# WaterLevelDisplay_v1-0.net
KiCad netlist of a schematic drawn in EAGLE
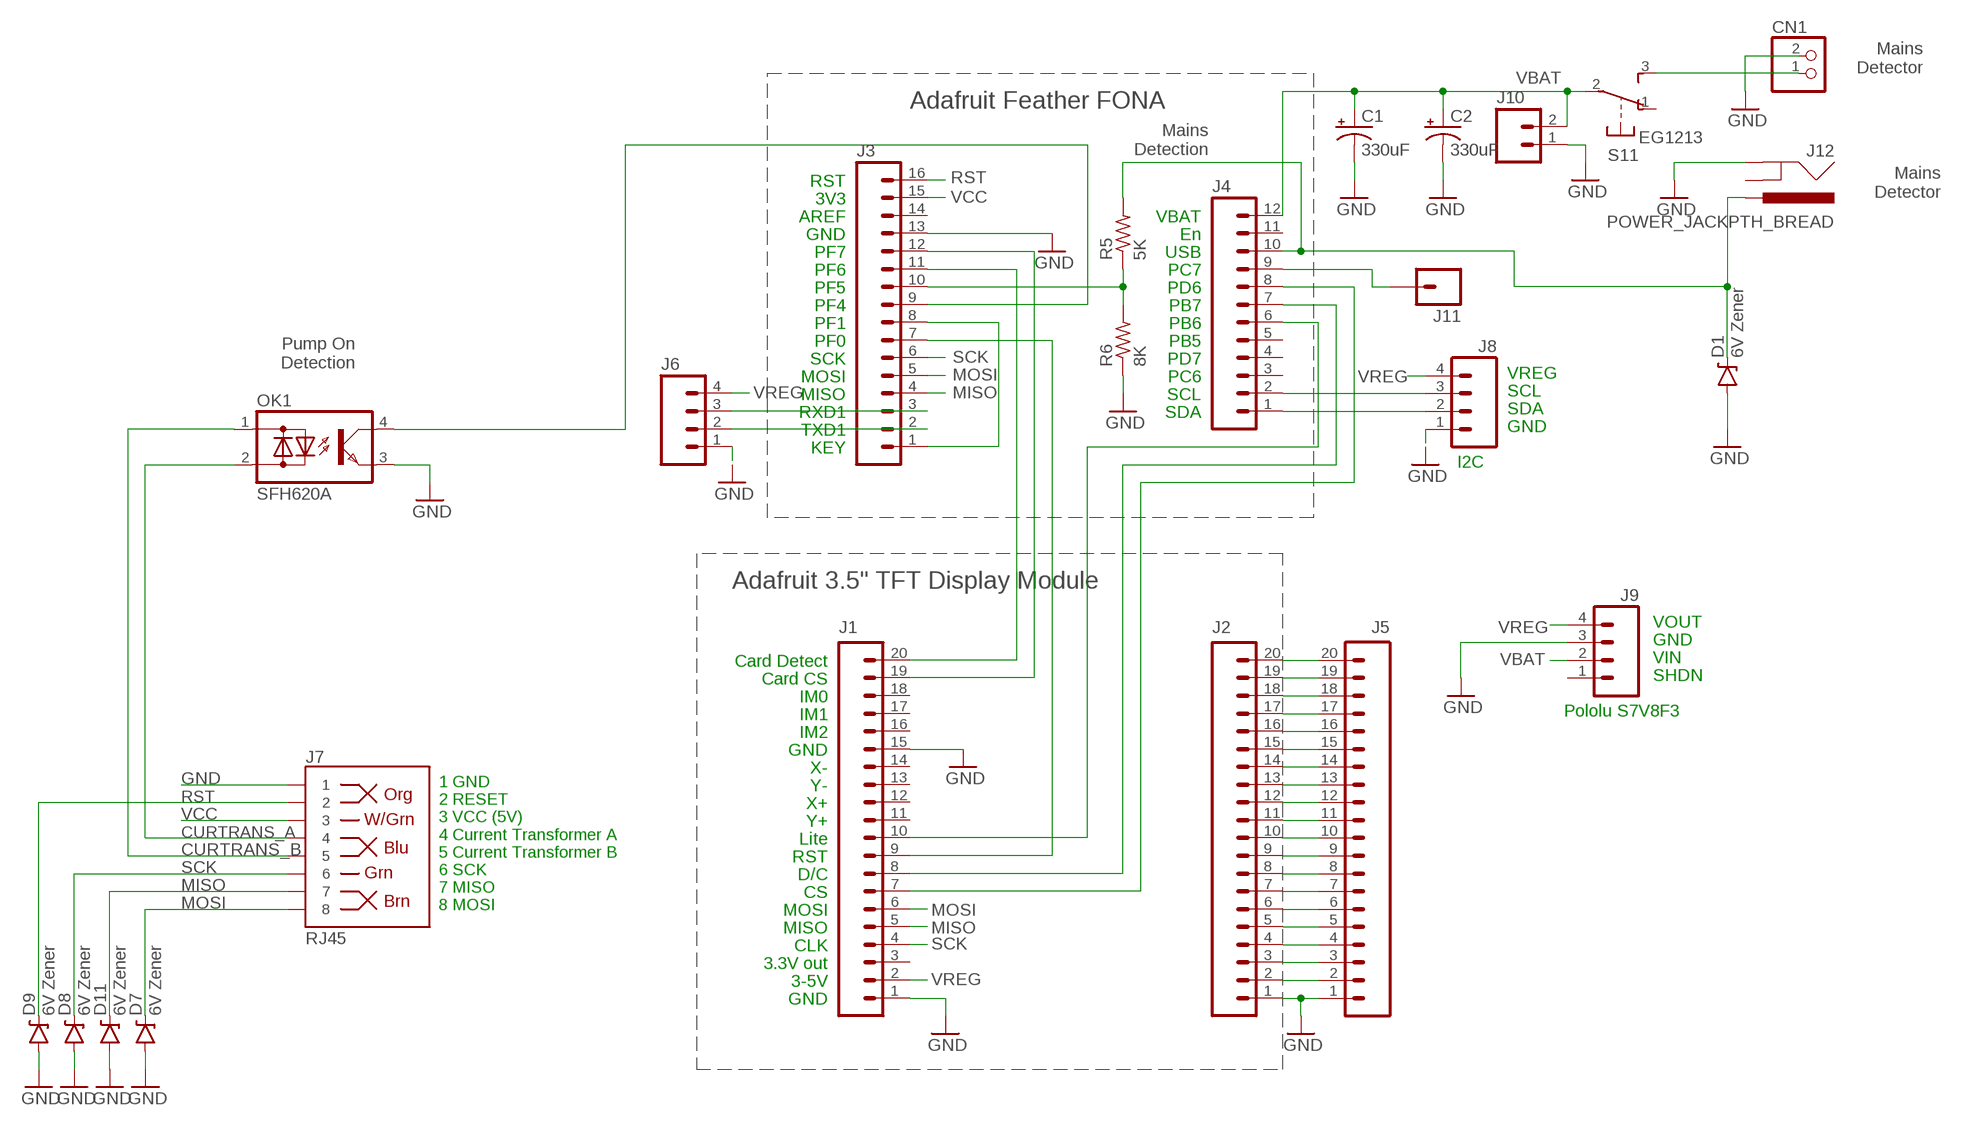
[diagram p0: schematic, sheet 1]

(export (version "E")
  (design (tool "Eeschema 10.0.6"))
  (components
    (comp (ref "C1")
      (value "330uF")
      (footprint "eagle-import:CPOL-RADIAL-100UF-25V")
      (libsource (lib "eagle-import") (part "CAP_POLPTH1"))
    )
    (comp (ref "C2")
      (value "330uF")
      (footprint "eagle-import:CPOL-RADIAL-100UF-25V")
      (libsource (lib "eagle-import") (part "CAP_POLPTH1"))
    )
    (comp (ref "CN1")
      (value "JST_2PIN-SMT-RA")
      (footprint "eagle-import:JST-PH-2-SMT-RA")
      (libsource (lib "eagle-import") (part "JST_2PIN-SMT-RA"))
    )
    (comp (ref "D1")
      (value "6V Zener")
      (footprint "eagle-import:DIODE-ZENER")
      (libsource (lib "eagle-import") (part "DIODE-ZENERPTH"))
    )
    (comp (ref "D7")
      (value "6V Zener")
      (footprint "eagle-import:DIODE-ZENER")
      (libsource (lib "eagle-import") (part "DIODE-ZENERPTH"))
    )
    (comp (ref "D8")
      (value "6V Zener")
      (footprint "eagle-import:DIODE-ZENER")
      (libsource (lib "eagle-import") (part "DIODE-ZENERPTH"))
    )
    (comp (ref "D9")
      (value "6V Zener")
      (footprint "eagle-import:DIODE-ZENER")
      (libsource (lib "eagle-import") (part "DIODE-ZENERPTH"))
    )
    (comp (ref "D11")
      (value "6V Zener")
      (footprint "eagle-import:DIODE-ZENER")
      (libsource (lib "eagle-import") (part "DIODE-ZENERPTH"))
    )
    (comp (ref "J1")
      (value "M20NOSILK")
      (footprint "eagle-import:1X20_NOSILK")
      (libsource (lib "eagle-import") (part "M20NOSILK"))
    )
    (comp (ref "J2")
      (value "M20NOSILK")
      (footprint "eagle-import:1X20_NOSILK")
      (libsource (lib "eagle-import") (part "M20NOSILK"))
    )
    (comp (ref "J3")
      (value "M161X16_NO_SILK")
      (footprint "eagle-import:1X16_NO_SILK")
      (libsource (lib "eagle-import") (part "M161X16_NO_SILK"))
    )
    (comp (ref "J4")
      (value "M12NO_SILK")
      (footprint "eagle-import:1X12_NO_SILK")
      (libsource (lib "eagle-import") (part "M12NO_SILK"))
    )
    (comp (ref "J5")
      (value "M20NOSILK")
      (footprint "eagle-import:1X20_NOSILK")
      (libsource (lib "eagle-import") (part "M20NOSILK"))
    )
    (comp (ref "J6")
      (value "M04PTH")
      (footprint "eagle-import:1X04")
      (libsource (lib "eagle-import") (part "M04PTH"))
    )
    (comp (ref "J7")
      (value "RJ45")
      (footprint "eagle-import:RJ45-8")
      (libsource (lib "eagle-import") (part "RJ45-8PTH"))
    )
    (comp (ref "J8")
      (value "M04PTH")
      (footprint "eagle-import:1X04")
      (libsource (lib "eagle-import") (part "M04PTH"))
    )
    (comp (ref "J9")
      (value "M04PTH")
      (footprint "eagle-import:1X04")
      (libsource (lib "eagle-import") (part "M04PTH"))
    )
    (comp (ref "J10")
      (value "M02PTH")
      (footprint "eagle-import:1X02")
      (libsource (lib "eagle-import") (part "M02PTH"))
    )
    (comp (ref "J11")
      (value "M01PTH")
      (footprint "eagle-import:1X01")
      (libsource (lib "eagle-import") (part "M01PTH"))
    )
    (comp (ref "J12")
      (value "POWER_JACKPTH_BREAD")
      (footprint "eagle-import:POWER_JACK_PTH_BREAD")
      (libsource (lib "eagle-import") (part "POWER_JACKPTH_BREAD"))
    )
    (comp (ref "OK1")
      (value "SFH620A")
      (footprint "eagle-import:DIL04")
      (fields (field (name "MPN") "SFH620A-2"))
      (libsource (lib "eagle-import") (part "SFH620A"))
    )
    (comp (ref "R5")
      (value "5K")
      (footprint "eagle-import:0204_5")
      (libsource (lib "eagle-import") (part "R-US_0204/5"))
    )
    (comp (ref "R6")
      (value "8K")
      (footprint "eagle-import:0204_5")
      (libsource (lib "eagle-import") (part "R-US_0204/5"))
    )
    (comp (ref "S1")
      (value "EG1213")
      (footprint "eagle-import:EG1213")
      (libsource (lib "eagle-import") (part "EG1213"))
    )
  )
  (nets
    (net (code "1") (name "/CURTRANS_A") (class "Default")
      (node (ref "J7") (pin "4") (pinfunction "4_4") (pintype "bidirectional"))
      (node (ref "OK1") (pin "2") (pinfunction "AC2_2") (pintype "passive"))
    )
    (net (code "2") (name "/CURTRANS_B") (class "Default")
      (node (ref "J7") (pin "5") (pinfunction "5_5") (pintype "bidirectional"))
      (node (ref "OK1") (pin "1") (pinfunction "AC1_1") (pintype "passive"))
    )
    (net (code "3") (name "/MISO") (class "Default")
      (node (ref "D11") (pin "P$1") (pinfunction "C_P$1") (pintype "passive"))
      (node (ref "J1") (pin "5") (pinfunction "5_5") (pintype "passive"))
      (node (ref "J3") (pin "4") (pinfunction "4_4") (pintype "passive"))
      (node (ref "J7") (pin "7") (pinfunction "7_7") (pintype "bidirectional"))
    )
    (net (code "4") (name "/MOSI") (class "Default")
      (node (ref "D7") (pin "P$1") (pinfunction "C_P$1") (pintype "passive"))
      (node (ref "J1") (pin "6") (pinfunction "6_6") (pintype "passive"))
      (node (ref "J3") (pin "5") (pinfunction "5_5") (pintype "passive"))
      (node (ref "J7") (pin "8") (pinfunction "8_8") (pintype "bidirectional"))
    )
    (net (code "5") (name "/RST") (class "Default")
      (node (ref "D9") (pin "P$1") (pinfunction "C_P$1") (pintype "passive"))
      (node (ref "J3") (pin "16") (pinfunction "16_16") (pintype "passive"))
      (node (ref "J7") (pin "2") (pinfunction "2_2") (pintype "bidirectional"))
    )
    (net (code "6") (name "/SCK") (class "Default")
      (node (ref "D8") (pin "P$1") (pinfunction "C_P$1") (pintype "passive"))
      (node (ref "J1") (pin "4") (pinfunction "4_4") (pintype "passive"))
      (node (ref "J3") (pin "6") (pinfunction "6_6") (pintype "passive"))
      (node (ref "J7") (pin "6") (pinfunction "6_6") (pintype "bidirectional"))
    )
    (net (code "7") (name "/VBAT") (class "Default")
      (node (ref "C1") (pin "1") (pinfunction "+_1") (pintype "passive"))
      (node (ref "C2") (pin "1") (pinfunction "+_1") (pintype "passive"))
      (node (ref "J10") (pin "2") (pinfunction "2_2") (pintype "passive"))
      (node (ref "J4") (pin "12") (pinfunction "12_12") (pintype "passive"))
      (node (ref "J9") (pin "2") (pinfunction "2_2") (pintype "passive"))
      (node (ref "S1") (pin "2") (pinfunction "P_2") (pintype "passive"))
    )
    (net (code "8") (name "/VCC") (class "Default")
      (node (ref "J3") (pin "15") (pinfunction "15_15") (pintype "passive"))
      (node (ref "J7") (pin "3") (pinfunction "3_3") (pintype "bidirectional"))
    )
    (net (code "9") (name "/VREG") (class "Default")
      (node (ref "J1") (pin "2") (pinfunction "2_2") (pintype "passive"))
      (node (ref "J6") (pin "4") (pinfunction "4_4") (pintype "passive"))
      (node (ref "J8") (pin "4") (pinfunction "4_4") (pintype "passive"))
      (node (ref "J9") (pin "4") (pinfunction "4_4") (pintype "passive"))
    )
    (net (code "10") (name "GND") (class "Default")
      (node (ref "C1") (pin "2") (pinfunction "-_2") (pintype "passive"))
      (node (ref "C2") (pin "2") (pinfunction "-_2") (pintype "passive"))
      (node (ref "CN1") (pin "2") (pinfunction "1_2") (pintype "passive"))
      (node (ref "D1") (pin "P$2") (pinfunction "A_P$2") (pintype "passive"))
      (node (ref "D11") (pin "P$2") (pinfunction "A_P$2") (pintype "passive"))
      (node (ref "D7") (pin "P$2") (pinfunction "A_P$2") (pintype "passive"))
      (node (ref "D8") (pin "P$2") (pinfunction "A_P$2") (pintype "passive"))
      (node (ref "D9") (pin "P$2") (pinfunction "A_P$2") (pintype "passive"))
      (node (ref "J1") (pin "1") (pinfunction "1_1") (pintype "passive"))
      (node (ref "J1") (pin "15") (pinfunction "15_15") (pintype "passive"))
      (node (ref "J10") (pin "1") (pinfunction "1_1") (pintype "passive"))
      (node (ref "J12") (pin "GND") (pinfunction "GND_GND") (pintype "bidirectional"))
      (node (ref "J2") (pin "1") (pinfunction "1_1") (pintype "passive"))
      (node (ref "J3") (pin "13") (pinfunction "13_13") (pintype "passive"))
      (node (ref "J5") (pin "1") (pinfunction "1_1") (pintype "passive"))
      (node (ref "J6") (pin "1") (pinfunction "1_1") (pintype "passive"))
      (node (ref "J7") (pin "1") (pinfunction "1_1") (pintype "bidirectional"))
      (node (ref "J8") (pin "1") (pinfunction "1_1") (pintype "passive"))
      (node (ref "J9") (pin "3") (pinfunction "3_3") (pintype "passive"))
      (node (ref "OK1") (pin "3") (pinfunction "E_3") (pintype "passive"))
      (node (ref "R6") (pin "1") (pinfunction "1_1") (pintype "passive"))
    )
    (net (code "11") (name "Net-(CN1-2)") (class "Default")
      (node (ref "CN1") (pin "1") (pinfunction "2_1") (pintype "passive"))
      (node (ref "S1") (pin "3") (pinfunction "S_3") (pintype "passive"))
    )
    (net (code "12") (name "Net-(D1-C)") (class "Default")
      (node (ref "D1") (pin "P$1") (pinfunction "C_P$1") (pintype "passive"))
      (node (ref "J12") (pin "PWR") (pinfunction "PWR_PWR") (pintype "bidirectional"))
      (node (ref "J4") (pin "10") (pinfunction "10_10") (pintype "passive"))
      (node (ref "R5") (pin "2") (pinfunction "2_2") (pintype "passive"))
    )
    (net (code "13") (name "Net-(J1-Pad7)") (class "Default")
      (node (ref "J1") (pin "7") (pinfunction "7_7") (pintype "passive"))
      (node (ref "J4") (pin "8") (pinfunction "8_8") (pintype "passive"))
    )
    (net (code "14") (name "Net-(J1-Pad8)") (class "Default")
      (node (ref "J1") (pin "8") (pinfunction "8_8") (pintype "passive"))
      (node (ref "J4") (pin "7") (pinfunction "7_7") (pintype "passive"))
    )
    (net (code "15") (name "Net-(J1-Pad9)") (class "Default")
      (node (ref "J1") (pin "9") (pinfunction "9_9") (pintype "passive"))
      (node (ref "J3") (pin "7") (pinfunction "7_7") (pintype "passive"))
    )
    (net (code "16") (name "Net-(J1-Pad10)") (class "Default")
      (node (ref "J1") (pin "10") (pinfunction "10_10") (pintype "passive"))
      (node (ref "J4") (pin "6") (pinfunction "6_6") (pintype "passive"))
    )
    (net (code "17") (name "Net-(J1-Pad19)") (class "Default")
      (node (ref "J1") (pin "19") (pinfunction "19_19") (pintype "passive"))
      (node (ref "J3") (pin "12") (pinfunction "12_12") (pintype "passive"))
    )
    (net (code "18") (name "Net-(J1-Pad20)") (class "Default")
      (node (ref "J1") (pin "20") (pinfunction "20_20") (pintype "passive"))
      (node (ref "J3") (pin "11") (pinfunction "11_11") (pintype "passive"))
    )
    (net (code "19") (name "Net-(J2-Pad2)") (class "Default")
      (node (ref "J2") (pin "2") (pinfunction "2_2") (pintype "passive"))
      (node (ref "J5") (pin "2") (pinfunction "2_2") (pintype "passive"))
    )
    (net (code "20") (name "Net-(J2-Pad3)") (class "Default")
      (node (ref "J2") (pin "3") (pinfunction "3_3") (pintype "passive"))
      (node (ref "J5") (pin "3") (pinfunction "3_3") (pintype "passive"))
    )
    (net (code "21") (name "Net-(J2-Pad4)") (class "Default")
      (node (ref "J2") (pin "4") (pinfunction "4_4") (pintype "passive"))
      (node (ref "J5") (pin "4") (pinfunction "4_4") (pintype "passive"))
    )
    (net (code "22") (name "Net-(J2-Pad5)") (class "Default")
      (node (ref "J2") (pin "5") (pinfunction "5_5") (pintype "passive"))
      (node (ref "J5") (pin "5") (pinfunction "5_5") (pintype "passive"))
    )
    (net (code "23") (name "Net-(J2-Pad6)") (class "Default")
      (node (ref "J2") (pin "6") (pinfunction "6_6") (pintype "passive"))
      (node (ref "J5") (pin "6") (pinfunction "6_6") (pintype "passive"))
    )
    (net (code "24") (name "Net-(J2-Pad7)") (class "Default")
      (node (ref "J2") (pin "7") (pinfunction "7_7") (pintype "passive"))
      (node (ref "J5") (pin "7") (pinfunction "7_7") (pintype "passive"))
    )
    (net (code "25") (name "Net-(J2-Pad8)") (class "Default")
      (node (ref "J2") (pin "8") (pinfunction "8_8") (pintype "passive"))
      (node (ref "J5") (pin "8") (pinfunction "8_8") (pintype "passive"))
    )
    (net (code "26") (name "Net-(J2-Pad9)") (class "Default")
      (node (ref "J2") (pin "9") (pinfunction "9_9") (pintype "passive"))
      (node (ref "J5") (pin "9") (pinfunction "9_9") (pintype "passive"))
    )
    (net (code "27") (name "Net-(J2-Pad10)") (class "Default")
      (node (ref "J2") (pin "10") (pinfunction "10_10") (pintype "passive"))
      (node (ref "J5") (pin "10") (pinfunction "10_10") (pintype "passive"))
    )
    (net (code "28") (name "Net-(J2-Pad11)") (class "Default")
      (node (ref "J2") (pin "11") (pinfunction "11_11") (pintype "passive"))
      (node (ref "J5") (pin "11") (pinfunction "11_11") (pintype "passive"))
    )
    (net (code "29") (name "Net-(J2-Pad12)") (class "Default")
      (node (ref "J2") (pin "12") (pinfunction "12_12") (pintype "passive"))
      (node (ref "J5") (pin "12") (pinfunction "12_12") (pintype "passive"))
    )
    (net (code "30") (name "Net-(J2-Pad13)") (class "Default")
      (node (ref "J2") (pin "13") (pinfunction "13_13") (pintype "passive"))
      (node (ref "J5") (pin "13") (pinfunction "13_13") (pintype "passive"))
    )
    (net (code "31") (name "Net-(J2-Pad14)") (class "Default")
      (node (ref "J2") (pin "14") (pinfunction "14_14") (pintype "passive"))
      (node (ref "J5") (pin "14") (pinfunction "14_14") (pintype "passive"))
    )
    (net (code "32") (name "Net-(J2-Pad15)") (class "Default")
      (node (ref "J2") (pin "15") (pinfunction "15_15") (pintype "passive"))
      (node (ref "J5") (pin "15") (pinfunction "15_15") (pintype "passive"))
    )
    (net (code "33") (name "Net-(J2-Pad16)") (class "Default")
      (node (ref "J2") (pin "16") (pinfunction "16_16") (pintype "passive"))
      (node (ref "J5") (pin "16") (pinfunction "16_16") (pintype "passive"))
    )
    (net (code "34") (name "Net-(J2-Pad17)") (class "Default")
      (node (ref "J2") (pin "17") (pinfunction "17_17") (pintype "passive"))
      (node (ref "J5") (pin "17") (pinfunction "17_17") (pintype "passive"))
    )
    (net (code "35") (name "Net-(J2-Pad18)") (class "Default")
      (node (ref "J2") (pin "18") (pinfunction "18_18") (pintype "passive"))
      (node (ref "J5") (pin "18") (pinfunction "18_18") (pintype "passive"))
    )
    (net (code "36") (name "Net-(J2-Pad19)") (class "Default")
      (node (ref "J2") (pin "19") (pinfunction "19_19") (pintype "passive"))
      (node (ref "J5") (pin "19") (pinfunction "19_19") (pintype "passive"))
    )
    (net (code "37") (name "Net-(J2-Pad20)") (class "Default")
      (node (ref "J2") (pin "20") (pinfunction "20_20") (pintype "passive"))
      (node (ref "J5") (pin "20") (pinfunction "20_20") (pintype "passive"))
    )
    (net (code "38") (name "Net-(J3-Pad1)") (class "Default")
      (node (ref "J3") (pin "1") (pinfunction "1_1") (pintype "passive"))
      (node (ref "J3") (pin "8") (pinfunction "8_8") (pintype "passive"))
    )
    (net (code "39") (name "Net-(J3-Pad2)") (class "Default")
      (node (ref "J3") (pin "2") (pinfunction "2_2") (pintype "passive"))
      (node (ref "J6") (pin "2") (pinfunction "2_2") (pintype "passive"))
    )
    (net (code "40") (name "Net-(J3-Pad3)") (class "Default")
      (node (ref "J3") (pin "3") (pinfunction "3_3") (pintype "passive"))
      (node (ref "J6") (pin "3") (pinfunction "3_3") (pintype "passive"))
    )
    (net (code "41") (name "Net-(J3-Pad10)") (class "Default")
      (node (ref "J3") (pin "10") (pinfunction "10_10") (pintype "passive"))
      (node (ref "R5") (pin "1") (pinfunction "1_1") (pintype "passive"))
      (node (ref "R6") (pin "2") (pinfunction "2_2") (pintype "passive"))
    )
    (net (code "42") (name "Net-(J4-Pad1)") (class "Default")
      (node (ref "J4") (pin "1") (pinfunction "1_1") (pintype "passive"))
      (node (ref "J8") (pin "2") (pinfunction "2_2") (pintype "passive"))
    )
    (net (code "43") (name "Net-(J4-Pad2)") (class "Default")
      (node (ref "J4") (pin "2") (pinfunction "2_2") (pintype "passive"))
      (node (ref "J8") (pin "3") (pinfunction "3_3") (pintype "passive"))
    )
    (net (code "44") (name "Net-(J11-Pad1)") (class "Default")
      (node (ref "J11") (pin "1") (pinfunction "1_1") (pintype "passive"))
      (node (ref "J4") (pin "9") (pinfunction "9_9") (pintype "passive"))
    )
    (net (code "45") (name "Net-(OK1-C)") (class "Default")
      (node (ref "J3") (pin "9") (pinfunction "9_9") (pintype "passive"))
      (node (ref "OK1") (pin "4") (pinfunction "C_4") (pintype "passive"))
    )
    (net (code "46") (name "unconnected-(J1-Pad3)") (class "Default")
      (node (ref "J1") (pin "3") (pinfunction "3_3") (pintype "passive"))
    )
    (net (code "47") (name "unconnected-(J1-Pad11)") (class "Default")
      (node (ref "J1") (pin "11") (pinfunction "11_11") (pintype "passive"))
    )
    (net (code "48") (name "unconnected-(J1-Pad12)") (class "Default")
      (node (ref "J1") (pin "12") (pinfunction "12_12") (pintype "passive"))
    )
    (net (code "49") (name "unconnected-(J1-Pad13)") (class "Default")
      (node (ref "J1") (pin "13") (pinfunction "13_13") (pintype "passive"))
    )
    (net (code "50") (name "unconnected-(J1-Pad14)") (class "Default")
      (node (ref "J1") (pin "14") (pinfunction "14_14") (pintype "passive"))
    )
    (net (code "51") (name "unconnected-(J1-Pad16)") (class "Default")
      (node (ref "J1") (pin "16") (pinfunction "16_16") (pintype "passive"))
    )
    (net (code "52") (name "unconnected-(J1-Pad17)") (class "Default")
      (node (ref "J1") (pin "17") (pinfunction "17_17") (pintype "passive"))
    )
    (net (code "53") (name "unconnected-(J1-Pad18)") (class "Default")
      (node (ref "J1") (pin "18") (pinfunction "18_18") (pintype "passive"))
    )
    (net (code "54") (name "unconnected-(J3-Pad14)") (class "Default")
      (node (ref "J3") (pin "14") (pinfunction "14_14") (pintype "passive"))
    )
    (net (code "55") (name "unconnected-(J4-Pad3)") (class "Default")
      (node (ref "J4") (pin "3") (pinfunction "3_3") (pintype "passive"))
    )
    (net (code "56") (name "unconnected-(J4-Pad4)") (class "Default")
      (node (ref "J4") (pin "4") (pinfunction "4_4") (pintype "passive"))
    )
    (net (code "57") (name "unconnected-(J4-Pad5)") (class "Default")
      (node (ref "J4") (pin "5") (pinfunction "5_5") (pintype "passive"))
    )
    (net (code "58") (name "unconnected-(J4-Pad11)") (class "Default")
      (node (ref "J4") (pin "11") (pinfunction "11_11") (pintype "passive"))
    )
    (net (code "59") (name "unconnected-(J9-Pad1)") (class "Default")
      (node (ref "J9") (pin "1") (pinfunction "1_1") (pintype "passive"))
    )
    (net (code "60") (name "unconnected-(J12-PadGNDBREAK)") (class "Default")
      (node (ref "J12") (pin "GNDBREAK") (pinfunction "GNDBREAK_GNDBREAK") (pintype "bidirectional"))
    )
    (net (code "61") (name "unconnected-(S1A-O-Pad1)") (class "Default")
      (node (ref "S1") (pin "1") (pinfunction "O_1") (pintype "passive"))
    )
  )
)
